# main_schematics.net
KiCad netlist of a schematic drawn in EAGLE
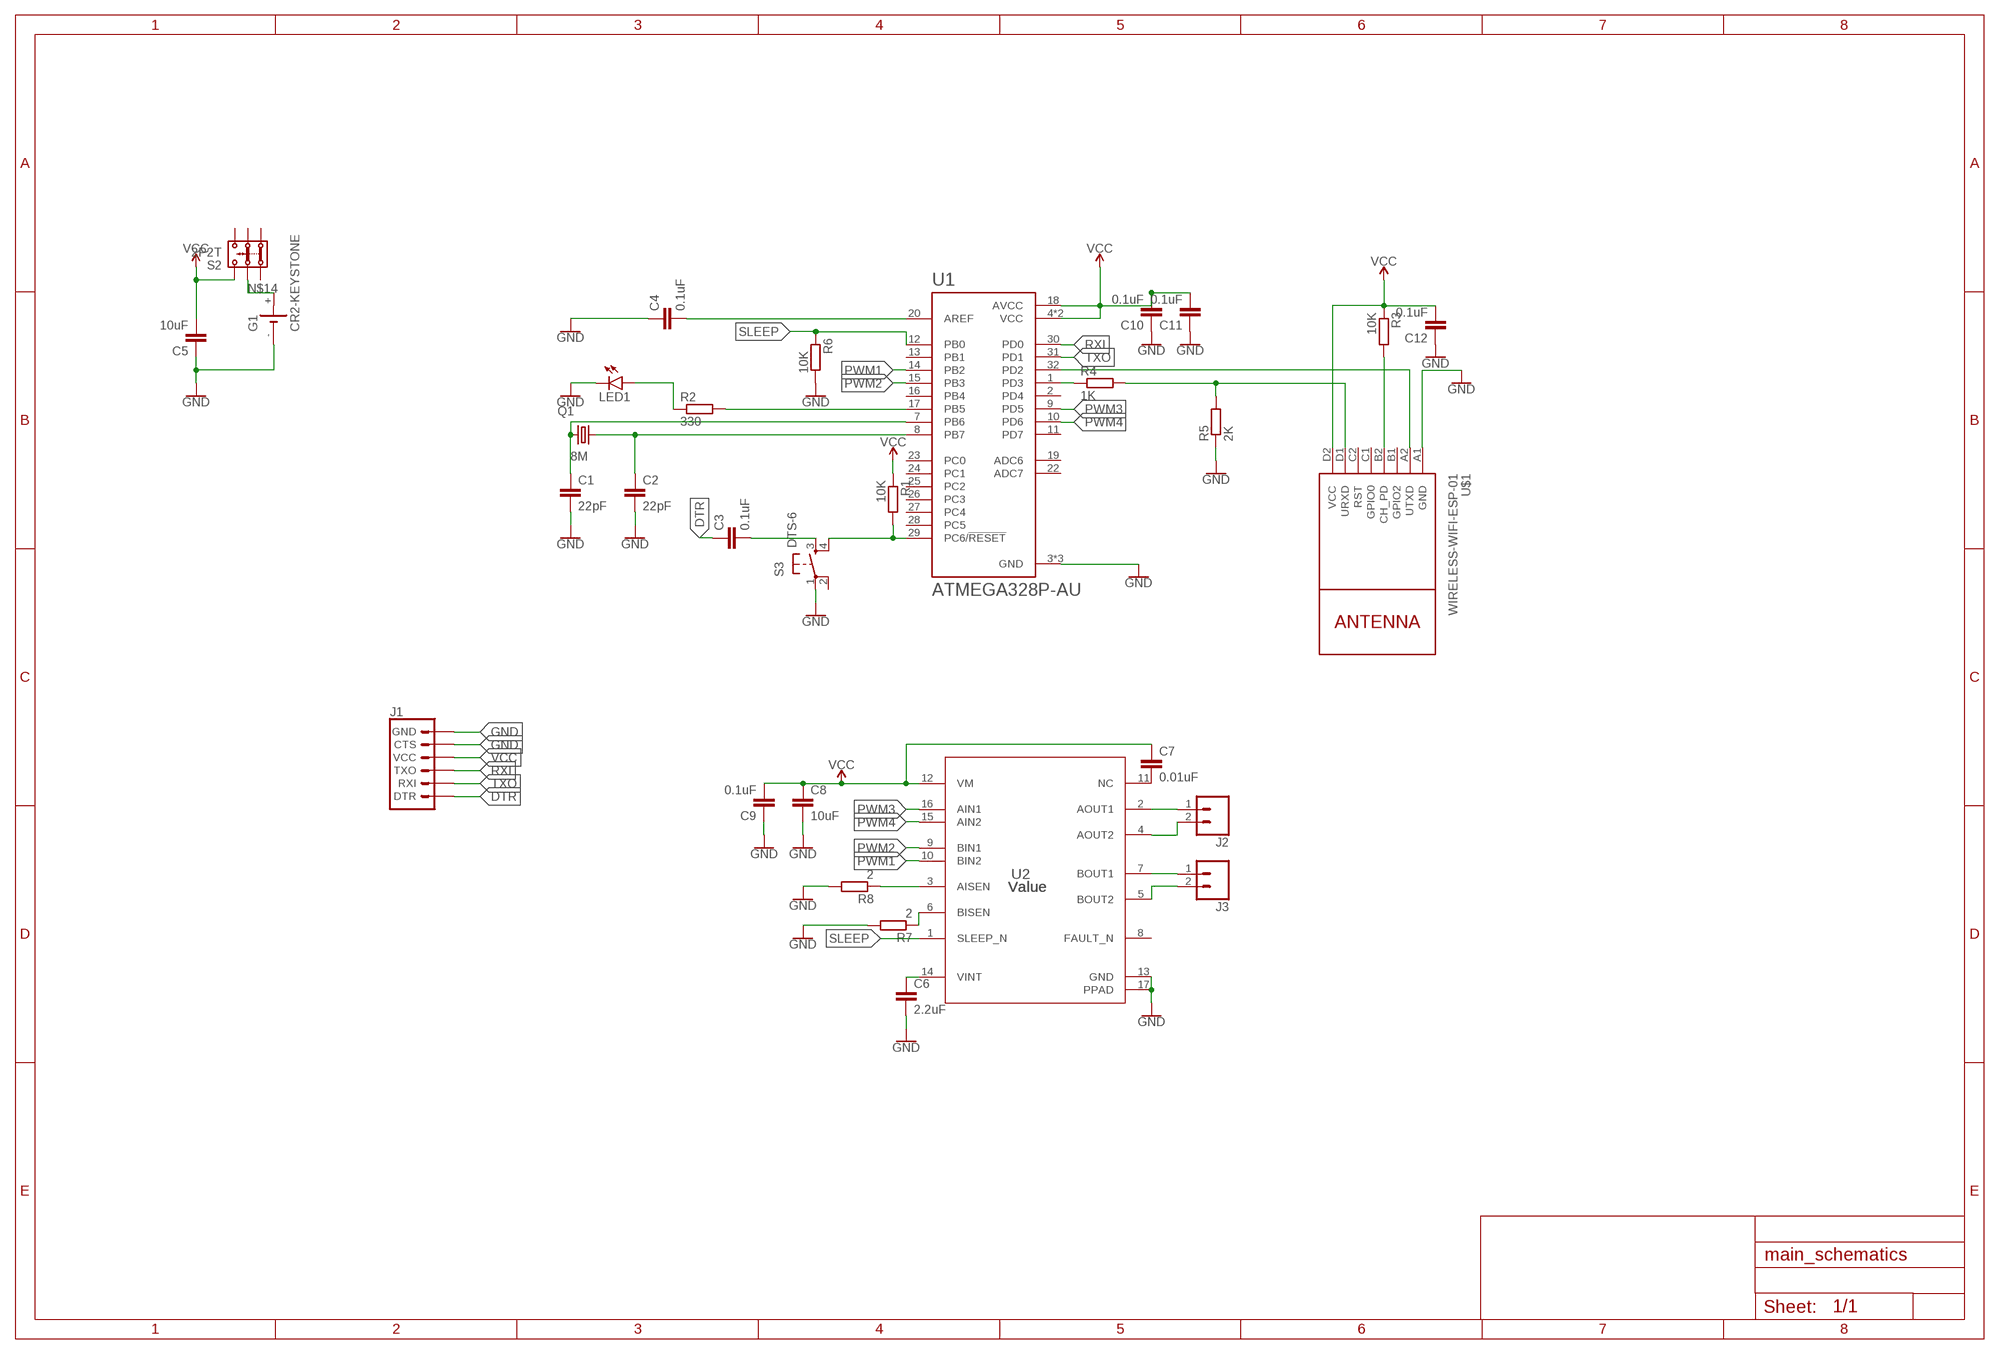
[diagram p0: schematic, sheet 1]

(export (version "E")
  (design (tool "Eeschema 10.0.6"))
  (components
    (comp (ref "C1")
      (value "22pF")
      (footprint "eagle-import:C0603")
      (libsource (lib "eagle-import") (part "C-EUC0603"))
    )
    (comp (ref "C2")
      (value "22pF")
      (footprint "eagle-import:C0603")
      (libsource (lib "eagle-import") (part "C-EUC0603"))
    )
    (comp (ref "C3")
      (value "0.1uF")
      (footprint "eagle-import:C0603")
      (libsource (lib "eagle-import") (part "C-EUC0603"))
    )
    (comp (ref "C4")
      (value "0.1uF")
      (footprint "eagle-import:C0603")
      (libsource (lib "eagle-import") (part "C-EUC0603"))
    )
    (comp (ref "C5")
      (value "10uF")
      (footprint "eagle-import:C0603")
      (libsource (lib "eagle-import") (part "C-EUC0603"))
    )
    (comp (ref "C6")
      (value "2.2uF")
      (footprint "eagle-import:C0603")
      (libsource (lib "eagle-import") (part "C-EUC0603"))
    )
    (comp (ref "C7")
      (value "0.01uF")
      (footprint "eagle-import:C0603")
      (libsource (lib "eagle-import") (part "C-EUC0603"))
    )
    (comp (ref "C8")
      (value "10uF")
      (footprint "eagle-import:C0603")
      (libsource (lib "eagle-import") (part "C-EUC0603"))
    )
    (comp (ref "C9")
      (value "0.1uF")
      (footprint "eagle-import:C0603")
      (libsource (lib "eagle-import") (part "C-EUC0603"))
    )
    (comp (ref "C10")
      (value "0.1uF")
      (footprint "eagle-import:C0603")
      (libsource (lib "eagle-import") (part "C-EUC0603"))
    )
    (comp (ref "C11")
      (value "0.1uF")
      (footprint "eagle-import:C0603")
      (libsource (lib "eagle-import") (part "C-EUC0603"))
    )
    (comp (ref "C12")
      (value "0.1uF")
      (footprint "eagle-import:C0603")
      (libsource (lib "eagle-import") (part "C-EUC0603"))
    )
    (comp (ref "G1")
      (value "CR2-KEYSTONE")
      (footprint "eagle-import:SL-150-1_2AA_PR")
      (libsource (lib "eagle-import") (part "CR2-KEYSTONE"))
    )
    (comp (ref "J1")
      (value "6_PIN_SERIAL_TARGETLONGPADS")
      (footprint "eagle-import:1X06_LONGPADS")
      (libsource (lib "eagle-import") (part "6_PIN_SERIAL_TARGETLONGPADS"))
    )
    (comp (ref "J2")
      (value "CONN_02POLAR")
      (footprint "eagle-import:MOLEX-1X2")
      (libsource (lib "eagle-import") (part "CONN_02POLAR"))
    )
    (comp (ref "J3")
      (value "CONN_02POLAR")
      (footprint "eagle-import:MOLEX-1X2")
      (libsource (lib "eagle-import") (part "CONN_02POLAR"))
    )
    (comp (ref "LED1")
      (value "LEDCHIP-LED0805")
      (footprint "eagle-import:CHIP-LED0805")
      (libsource (lib "eagle-import") (part "LEDCHIP-LED0805"))
    )
    (comp (ref "Q1")
      (value "8M")
      (footprint "eagle-import:CSM-7X-DU")
      (libsource (lib "eagle-import") (part "CSM-7X-DU"))
    )
    (comp (ref "R1")
      (value "10K")
      (footprint "eagle-import:R0603")
      (libsource (lib "eagle-import") (part "R-EU_R0603"))
    )
    (comp (ref "R2")
      (value "330")
      (footprint "eagle-import:R0603")
      (libsource (lib "eagle-import") (part "R-EU_R0603"))
    )
    (comp (ref "R3")
      (value "10K")
      (footprint "eagle-import:R0603")
      (libsource (lib "eagle-import") (part "R-EU_R0603"))
    )
    (comp (ref "R4")
      (value "1K")
      (footprint "eagle-import:R0603")
      (libsource (lib "eagle-import") (part "R-EU_R0603"))
    )
    (comp (ref "R5")
      (value "2K")
      (footprint "eagle-import:R0603")
      (libsource (lib "eagle-import") (part "R-EU_R0603"))
    )
    (comp (ref "R6")
      (value "10K")
      (footprint "eagle-import:R0603")
      (libsource (lib "eagle-import") (part "R-EU_R0603"))
    )
    (comp (ref "R7")
      (value "2")
      (footprint "eagle-import:R0603")
      (libsource (lib "eagle-import") (part "R-EU_R0603"))
    )
    (comp (ref "R8")
      (value "2")
      (footprint "eagle-import:R0603")
      (libsource (lib "eagle-import") (part "R-EU_R0603"))
    )
    (comp (ref "S2")
      (value "2P2T")
      (footprint "eagle-import:2P2T")
      (libsource (lib "eagle-import") (part "2P2T"))
    )
    (comp (ref "S3")
      (value "DTS-6")
      (footprint "eagle-import:DTS-6")
      (libsource (lib "eagle-import") (part "DTS-6"))
    )
    (comp (ref "U$1")
      (value "WIRELESS-WIFI-ESP-01")
      (footprint "eagle-import:WIRELESS-WIFI-ESP-01")
      (libsource (lib "eagle-import") (part "WIRELESS-WIFI-ESP-01"))
    )
    (comp (ref "U1")
      (value "ATMEGA328P-AU")
      (footprint "eagle-import:QFP80P900X900X120-32N")
      (fields (field (name "MF") "Microchip"))
      (libsource (lib "eagle-import") (part "ATMEGA328P-AU"))
    )
    (comp (ref "U2")
      (value "Value")
      (footprint "eagle-import:PWP0016K_M")
      (fields (field (name "MANUFACTURER") "Texas Instruments") (field (name "PARTNUMBER") "DRV8833CPWPR"))
      (libsource (lib "eagle-import") (part "DRV8833CPWPPWP0016K_M"))
    )
  )
  (nets
    (net (code "1") (name "/N$14") (class "Default")
      (node (ref "G1") (pin "+") (pinfunction "+_+") (pintype "passive"))
      (node (ref "S2") (pin "2.1") (pinfunction "2.1_2.1") (pintype "passive"))
    )
    (net (code "2") (name "DTR") (class "Default")
      (node (ref "C3") (pin "1") (pinfunction "1_1") (pintype "passive"))
      (node (ref "J1") (pin "1") (pinfunction "DTR_1") (pintype "passive"))
    )
    (net (code "3") (name "GND") (class "Default")
      (node (ref "C1") (pin "2") (pinfunction "2_2") (pintype "passive"))
      (node (ref "C10") (pin "1") (pinfunction "1_1") (pintype "passive"))
      (node (ref "C11") (pin "1") (pinfunction "1_1") (pintype "passive"))
      (node (ref "C12") (pin "1") (pinfunction "1_1") (pintype "passive"))
      (node (ref "C2") (pin "2") (pinfunction "2_2") (pintype "passive"))
      (node (ref "C4") (pin "1") (pinfunction "1_1") (pintype "passive"))
      (node (ref "C5") (pin "1") (pinfunction "1_1") (pintype "passive"))
      (node (ref "C6") (pin "2") (pinfunction "2_2") (pintype "passive"))
      (node (ref "C8") (pin "2") (pinfunction "2_2") (pintype "passive"))
      (node (ref "C9") (pin "1") (pinfunction "1_1") (pintype "passive"))
      (node (ref "G1") (pin "-") (pinfunction "-_-") (pintype "passive"))
      (node (ref "J1") (pin "5") (pinfunction "CTS_5") (pintype "passive"))
      (node (ref "J1") (pin "6") (pinfunction "GND_6") (pintype "passive"))
      (node (ref "LED1") (pin "C") (pinfunction "C_C") (pintype "passive"))
      (node (ref "R5") (pin "1") (pinfunction "1_1") (pintype "passive"))
      (node (ref "R6") (pin "2") (pinfunction "2_2") (pintype "passive"))
      (node (ref "R7") (pin "2") (pinfunction "2_2") (pintype "passive"))
      (node (ref "R8") (pin "2") (pinfunction "2_2") (pintype "passive"))
      (node (ref "S3") (pin "1") (pinfunction "1_1") (pintype "passive"))
      (node (ref "U$1") (pin "A1") (pinfunction "GND_A1") (pintype "power_in"))
      (node (ref "U1") (pin "21") (pinfunction "GND_21") (pintype "power_in"))
      (node (ref "U1") (pin "3") (pinfunction "GND_3") (pintype "power_in"))
      (node (ref "U1") (pin "5") (pinfunction "GND_5") (pintype "power_in"))
      (node (ref "U2") (pin "13") (pinfunction "GND_13") (pintype "power_in"))
      (node (ref "U2") (pin "17") (pinfunction "PPAD_17") (pintype "power_in"))
    )
    (net (code "4") (name "Net-(C3-Pad2)") (class "Default")
      (node (ref "C3") (pin "2") (pinfunction "2_2") (pintype "passive"))
      (node (ref "S3") (pin "3") (pinfunction "3_3") (pintype "passive"))
    )
    (net (code "5") (name "Net-(LED1-PadA)") (class "Default")
      (node (ref "LED1") (pin "A") (pinfunction "A_A") (pintype "passive"))
      (node (ref "R2") (pin "1") (pinfunction "1_1") (pintype "passive"))
    )
    (net (code "6") (name "Net-(U$1-CH_PD)") (class "Default")
      (node (ref "R3") (pin "2") (pinfunction "2_2") (pintype "passive"))
      (node (ref "U$1") (pin "B2") (pinfunction "CH_PD_B2") (pintype "bidirectional"))
    )
    (net (code "7") (name "Net-(U$1-URXD)") (class "Default")
      (node (ref "R4") (pin "2") (pinfunction "2_2") (pintype "passive"))
      (node (ref "R5") (pin "2") (pinfunction "2_2") (pintype "passive"))
      (node (ref "U$1") (pin "D1") (pinfunction "URXD_D1") (pintype "bidirectional"))
    )
    (net (code "8") (name "Net-(U$1-UTXD)") (class "Default")
      (node (ref "U$1") (pin "A2") (pinfunction "UTXD_A2") (pintype "bidirectional"))
      (node (ref "U1") (pin "32") (pinfunction "PD2_32") (pintype "bidirectional"))
    )
    (net (code "9") (name "Net-(U1-AREF)") (class "Default")
      (node (ref "C4") (pin "2") (pinfunction "2_2") (pintype "passive"))
      (node (ref "U1") (pin "20") (pinfunction "AREF_20") (pintype "input"))
    )
    (net (code "10") (name "Net-(U1-PB5)") (class "Default")
      (node (ref "R2") (pin "2") (pinfunction "2_2") (pintype "passive"))
      (node (ref "U1") (pin "17") (pinfunction "PB5_17") (pintype "bidirectional"))
    )
    (net (code "11") (name "Net-(U1-PB6)") (class "Default")
      (node (ref "C1") (pin "1") (pinfunction "1_1") (pintype "passive"))
      (node (ref "Q1") (pin "1") (pinfunction "1_1") (pintype "passive"))
      (node (ref "U1") (pin "7") (pinfunction "PB6_7") (pintype "bidirectional"))
    )
    (net (code "12") (name "Net-(U1-PB7)") (class "Default")
      (node (ref "C2") (pin "1") (pinfunction "1_1") (pintype "passive"))
      (node (ref "Q1") (pin "2") (pinfunction "2_2") (pintype "passive"))
      (node (ref "U1") (pin "8") (pinfunction "PB7_8") (pintype "bidirectional"))
    )
    (net (code "13") (name "Net-(U1-PC6{slash}~{RESET})") (class "Default")
      (node (ref "R1") (pin "2") (pinfunction "2_2") (pintype "passive"))
      (node (ref "S3") (pin "4") (pinfunction "4_4") (pintype "passive"))
      (node (ref "U1") (pin "29") (pinfunction "PC6/~{RESET}_29") (pintype "bidirectional"))
    )
    (net (code "14") (name "Net-(U1-PD3)") (class "Default")
      (node (ref "R4") (pin "1") (pinfunction "1_1") (pintype "passive"))
      (node (ref "U1") (pin "1") (pinfunction "PD3_1") (pintype "bidirectional"))
    )
    (net (code "15") (name "Net-(U2-AISEN)") (class "Default")
      (node (ref "R8") (pin "1") (pinfunction "1_1") (pintype "passive"))
      (node (ref "U2") (pin "3") (pinfunction "AISEN_3") (pintype "input"))
    )
    (net (code "16") (name "Net-(U2-AOUT1)") (class "Default")
      (node (ref "J2") (pin "1") (pinfunction "1_1") (pintype "passive"))
      (node (ref "U2") (pin "2") (pinfunction "AOUT1_2") (pintype "tri_state"))
    )
    (net (code "17") (name "Net-(U2-AOUT2)") (class "Default")
      (node (ref "J2") (pin "2") (pinfunction "2_2") (pintype "passive"))
      (node (ref "U2") (pin "4") (pinfunction "AOUT2_4") (pintype "tri_state"))
    )
    (net (code "18") (name "Net-(U2-BISEN)") (class "Default")
      (node (ref "R7") (pin "1") (pinfunction "1_1") (pintype "passive"))
      (node (ref "U2") (pin "6") (pinfunction "BISEN_6") (pintype "input"))
    )
    (net (code "19") (name "Net-(U2-BOUT1)") (class "Default")
      (node (ref "J3") (pin "1") (pinfunction "1_1") (pintype "passive"))
      (node (ref "U2") (pin "7") (pinfunction "BOUT1_7") (pintype "tri_state"))
    )
    (net (code "20") (name "Net-(U2-BOUT2)") (class "Default")
      (node (ref "J3") (pin "2") (pinfunction "2_2") (pintype "passive"))
      (node (ref "U2") (pin "5") (pinfunction "BOUT2_5") (pintype "tri_state"))
    )
    (net (code "21") (name "Net-(U2-NC)") (class "Default")
      (node (ref "C7") (pin "2") (pinfunction "2_2") (pintype "passive"))
      (node (ref "U2") (pin "11") (pinfunction "NC_11") (pintype "passive"))
    )
    (net (code "22") (name "Net-(U2-VINT)") (class "Default")
      (node (ref "C6") (pin "1") (pinfunction "1_1") (pintype "passive"))
      (node (ref "U2") (pin "14") (pinfunction "VINT_14") (pintype "passive"))
    )
    (net (code "23") (name "PWM1") (class "Default")
      (node (ref "U1") (pin "14") (pinfunction "PB2_14") (pintype "bidirectional"))
      (node (ref "U2") (pin "10") (pinfunction "BIN2_10") (pintype "input"))
    )
    (net (code "24") (name "PWM2") (class "Default")
      (node (ref "U1") (pin "15") (pinfunction "PB3_15") (pintype "bidirectional"))
      (node (ref "U2") (pin "9") (pinfunction "BIN1_9") (pintype "input"))
    )
    (net (code "25") (name "PWM3") (class "Default")
      (node (ref "U1") (pin "9") (pinfunction "PD5_9") (pintype "bidirectional"))
      (node (ref "U2") (pin "16") (pinfunction "AIN1_16") (pintype "input"))
    )
    (net (code "26") (name "PWM4") (class "Default")
      (node (ref "U1") (pin "10") (pinfunction "PD6_10") (pintype "bidirectional"))
      (node (ref "U2") (pin "15") (pinfunction "AIN2_15") (pintype "input"))
    )
    (net (code "27") (name "RXI") (class "Default")
      (node (ref "J1") (pin "3") (pinfunction "TXO_3") (pintype "passive"))
      (node (ref "U1") (pin "30") (pinfunction "PD0_30") (pintype "bidirectional"))
    )
    (net (code "28") (name "SLEEP") (class "Default")
      (node (ref "R6") (pin "1") (pinfunction "1_1") (pintype "passive"))
      (node (ref "U1") (pin "12") (pinfunction "PB0_12") (pintype "bidirectional"))
      (node (ref "U2") (pin "1") (pinfunction "SLEEP_N_1") (pintype "input"))
    )
    (net (code "29") (name "TXO") (class "Default")
      (node (ref "J1") (pin "2") (pinfunction "RXI_2") (pintype "passive"))
      (node (ref "U1") (pin "31") (pinfunction "PD1_31") (pintype "bidirectional"))
    )
    (net (code "30") (name "VCC") (class "Default")
      (node (ref "C10") (pin "2") (pinfunction "2_2") (pintype "passive"))
      (node (ref "C11") (pin "2") (pinfunction "2_2") (pintype "passive"))
      (node (ref "C12") (pin "2") (pinfunction "2_2") (pintype "passive"))
      (node (ref "C5") (pin "2") (pinfunction "2_2") (pintype "passive"))
      (node (ref "C7") (pin "1") (pinfunction "1_1") (pintype "passive"))
      (node (ref "C8") (pin "1") (pinfunction "1_1") (pintype "passive"))
      (node (ref "C9") (pin "2") (pinfunction "2_2") (pintype "passive"))
      (node (ref "J1") (pin "4") (pinfunction "VCC_4") (pintype "passive"))
      (node (ref "R1") (pin "1") (pinfunction "1_1") (pintype "passive"))
      (node (ref "R3") (pin "1") (pinfunction "1_1") (pintype "passive"))
      (node (ref "S2") (pin "3.1") (pinfunction "3.1_3.1") (pintype "passive"))
      (node (ref "U$1") (pin "D2") (pinfunction "VCC_D2") (pintype "power_in"))
      (node (ref "U1") (pin "18") (pinfunction "AVCC_18") (pintype "power_in"))
      (node (ref "U1") (pin "4") (pinfunction "VCC_4") (pintype "power_in"))
      (node (ref "U1") (pin "6") (pinfunction "VCC_6") (pintype "power_in"))
      (node (ref "U2") (pin "12") (pinfunction "VM_12") (pintype "power_in"))
    )
    (net (code "31") (name "unconnected-(S2-Pad1.1)") (class "Default")
      (node (ref "S2") (pin "1.1") (pinfunction "1.1_1.1") (pintype "passive"))
    )
    (net (code "32") (name "unconnected-(S2-Pad1.2)") (class "Default")
      (node (ref "S2") (pin "1.2") (pinfunction "1.2_1.2") (pintype "passive"))
    )
    (net (code "33") (name "unconnected-(S2-Pad2.2)") (class "Default")
      (node (ref "S2") (pin "2.2") (pinfunction "2.2_2.2") (pintype "passive"))
    )
    (net (code "34") (name "unconnected-(S2-Pad3.2)") (class "Default")
      (node (ref "S2") (pin "3.2") (pinfunction "3.2_3.2") (pintype "passive"))
    )
    (net (code "35") (name "unconnected-(S3-Pad2)") (class "Default")
      (node (ref "S3") (pin "2") (pinfunction "2_2") (pintype "passive"))
    )
    (net (code "36") (name "unconnected-(U$1-GPIO0-PadC1)") (class "Default")
      (node (ref "U$1") (pin "C1") (pinfunction "GPIO0_C1") (pintype "bidirectional"))
    )
    (net (code "37") (name "unconnected-(U$1-GPIO2-PadB1)") (class "Default")
      (node (ref "U$1") (pin "B1") (pinfunction "GPIO2_B1") (pintype "bidirectional"))
    )
    (net (code "38") (name "unconnected-(U$1-RST-PadC2)") (class "Default")
      (node (ref "U$1") (pin "C2") (pinfunction "RST_C2") (pintype "bidirectional"))
    )
    (net (code "39") (name "unconnected-(U1-ADC6-Pad19)") (class "Default")
      (node (ref "U1") (pin "19") (pinfunction "ADC6_19") (pintype "bidirectional"))
    )
    (net (code "40") (name "unconnected-(U1-ADC7-Pad22)") (class "Default")
      (node (ref "U1") (pin "22") (pinfunction "ADC7_22") (pintype "bidirectional"))
    )
    (net (code "41") (name "unconnected-(U1-PB1-Pad13)") (class "Default")
      (node (ref "U1") (pin "13") (pinfunction "PB1_13") (pintype "bidirectional"))
    )
    (net (code "42") (name "unconnected-(U1-PB4-Pad16)") (class "Default")
      (node (ref "U1") (pin "16") (pinfunction "PB4_16") (pintype "bidirectional"))
    )
    (net (code "43") (name "unconnected-(U1-PC0-Pad23)") (class "Default")
      (node (ref "U1") (pin "23") (pinfunction "PC0_23") (pintype "bidirectional"))
    )
    (net (code "44") (name "unconnected-(U1-PC1-Pad24)") (class "Default")
      (node (ref "U1") (pin "24") (pinfunction "PC1_24") (pintype "bidirectional"))
    )
    (net (code "45") (name "unconnected-(U1-PC2-Pad25)") (class "Default")
      (node (ref "U1") (pin "25") (pinfunction "PC2_25") (pintype "bidirectional"))
    )
    (net (code "46") (name "unconnected-(U1-PC3-Pad26)") (class "Default")
      (node (ref "U1") (pin "26") (pinfunction "PC3_26") (pintype "bidirectional"))
    )
    (net (code "47") (name "unconnected-(U1-PC4-Pad27)") (class "Default")
      (node (ref "U1") (pin "27") (pinfunction "PC4_27") (pintype "bidirectional"))
    )
    (net (code "48") (name "unconnected-(U1-PC5-Pad28)") (class "Default")
      (node (ref "U1") (pin "28") (pinfunction "PC5_28") (pintype "bidirectional"))
    )
    (net (code "49") (name "unconnected-(U1-PD4-Pad2)") (class "Default")
      (node (ref "U1") (pin "2") (pinfunction "PD4_2") (pintype "bidirectional"))
    )
    (net (code "50") (name "unconnected-(U1-PD7-Pad11)") (class "Default")
      (node (ref "U1") (pin "11") (pinfunction "PD7_11") (pintype "bidirectional"))
    )
    (net (code "51") (name "unconnected-(U2-FAULT_N-Pad8)") (class "Default")
      (node (ref "U2") (pin "8") (pinfunction "FAULT_N_8") (pintype "open_collector"))
    )
  )
)
